# Gate_Connect.net
KiCad netlist of a schematic drawn in Altium Designer
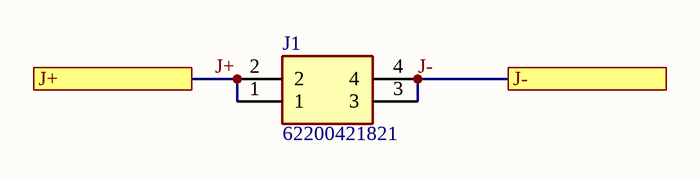
[diagram p0: Gate Connect.SchDoc]

(export (version "E")
  (design (tool "Eeschema 10.0.6"))
  (components
    (comp (ref "J1")
      (value "62200421821")
      (footprint "SamacSys:62200421821")
      (description "Connector")
      (fields (field (name "MOUSER PART NUMBER") "710-62200421821"))
      (libsource (lib "*") (part "62200421821"))
    )
  )
  (nets
    (net (code "1") (name "/J+") (class "Default")
      (node (ref "J1") (pin "1") (pinfunction "1_1") (pintype "passive"))
      (node (ref "J1") (pin "2") (pinfunction "2_2") (pintype "passive"))
    )
    (net (code "2") (name "/J-") (class "Default")
      (node (ref "J1") (pin "3") (pinfunction "3_3") (pintype "passive"))
      (node (ref "J1") (pin "4") (pinfunction "4_4") (pintype "passive"))
    )
  )
)
